# booz_imu.net
KiCad netlist of a schematic drawn in EAGLE
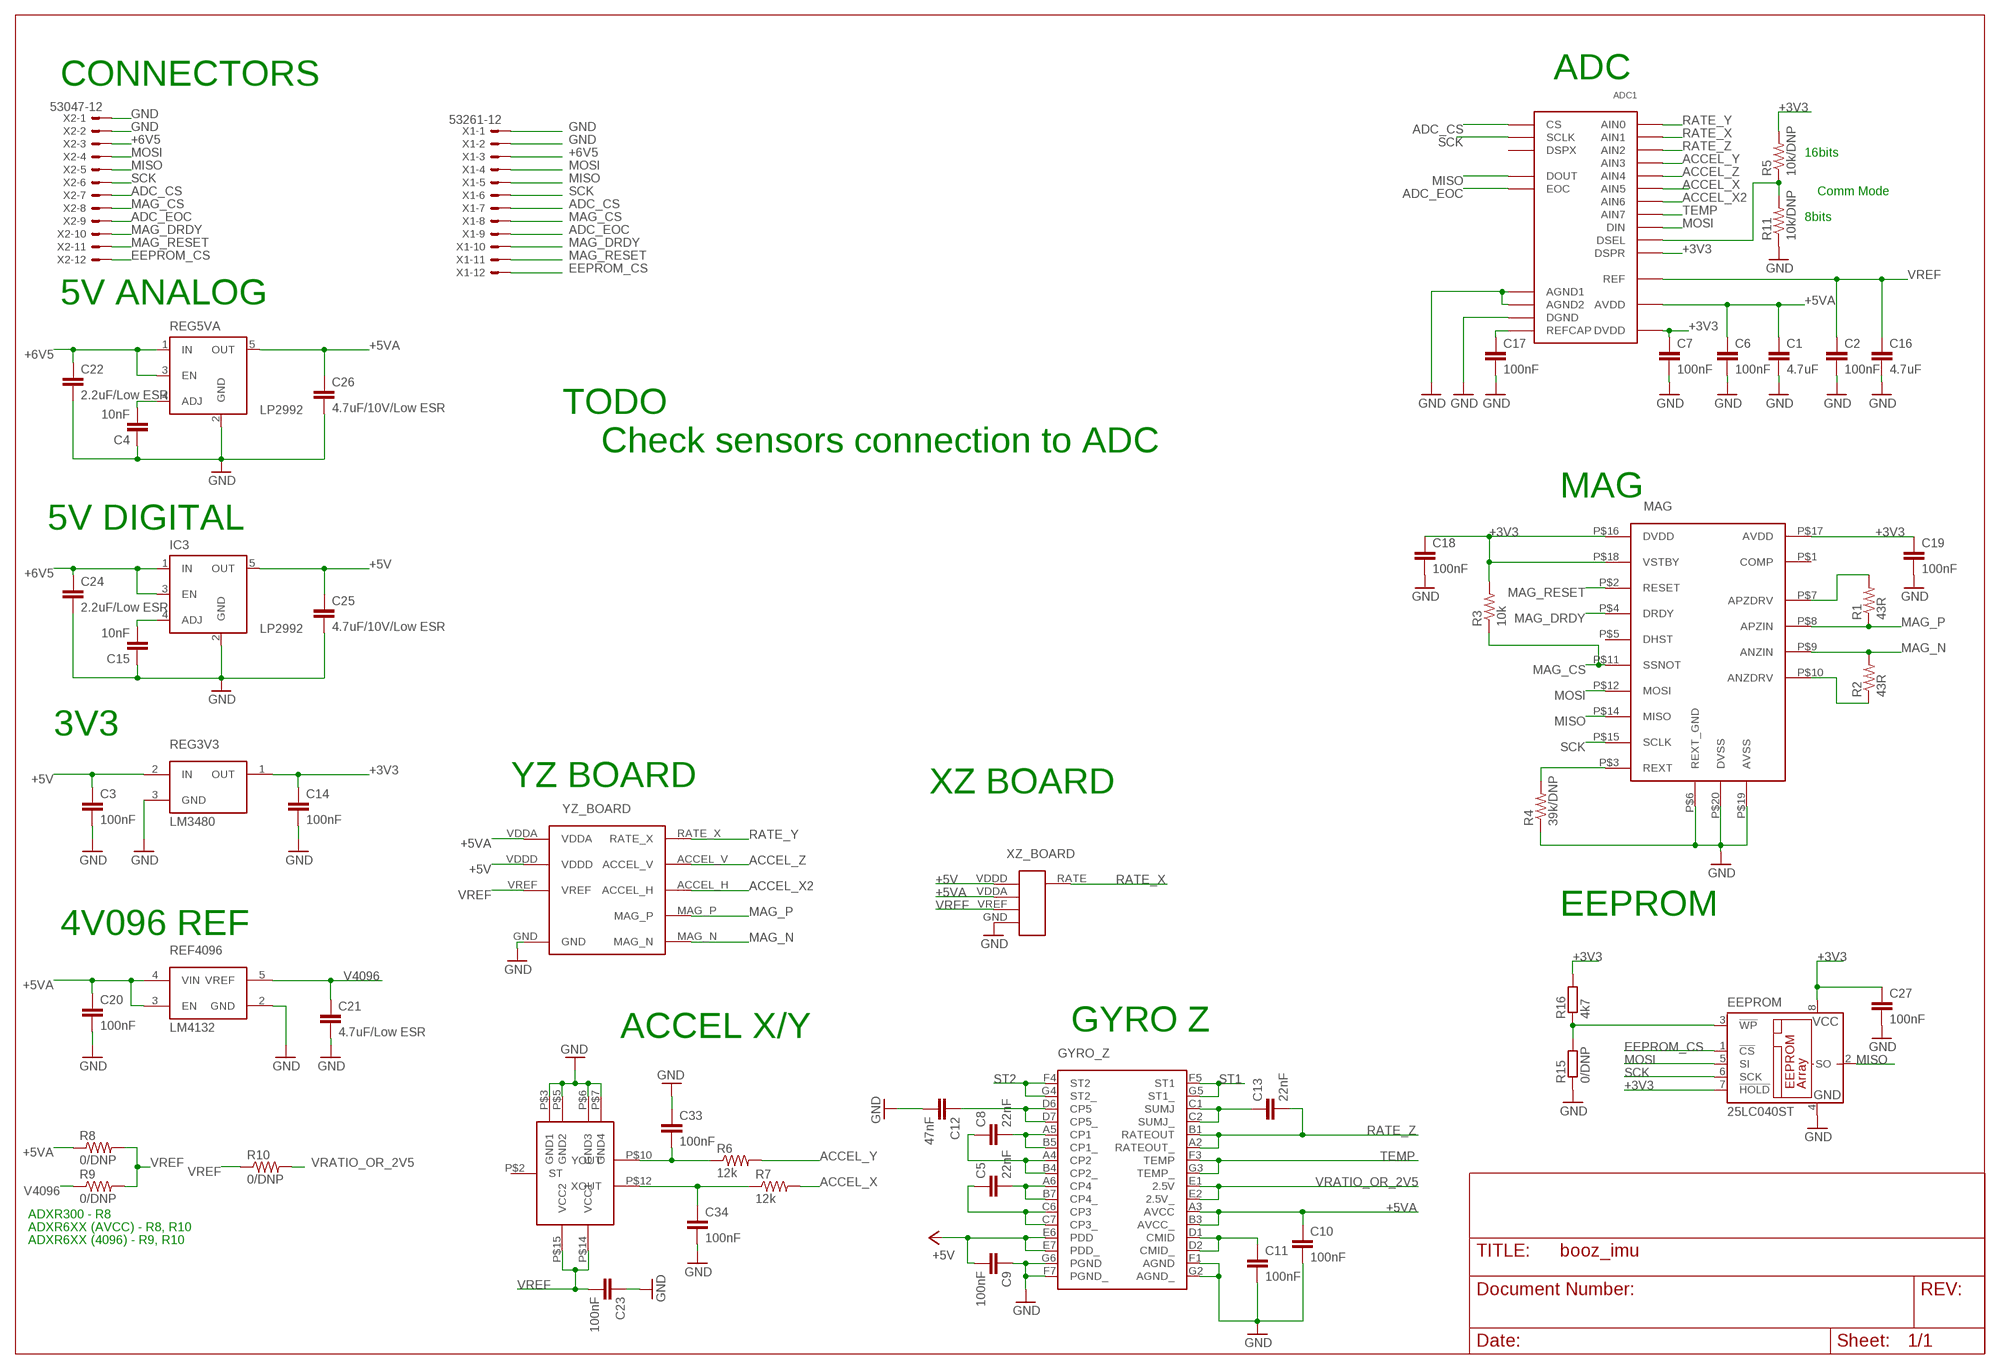
[diagram p0: schematic, sheet 1]

(export (version "E")
  (design (tool "Eeschema 10.0.6"))
  (components
    (comp (ref "ADC1")
      (value "MAX1168")
      (footprint "eagle-import:QSOP24")
      (libsource (lib "eagle-import") (part "MAX1168"))
    )
    (comp (ref "C1")
      (value "4.7uF")
      (footprint "eagle-import:C0805")
      (libsource (lib "eagle-import") (part "C-EUC0805"))
    )
    (comp (ref "C2")
      (value "100nF")
      (footprint "eagle-import:C0603K")
      (libsource (lib "eagle-import") (part "C-EUC0603K"))
    )
    (comp (ref "C3")
      (value "100nF")
      (footprint "eagle-import:C0603K")
      (libsource (lib "eagle-import") (part "C-EUC0603K"))
    )
    (comp (ref "C4")
      (value "10nF")
      (footprint "eagle-import:C0603K")
      (libsource (lib "eagle-import") (part "C-EUC0603K"))
    )
    (comp (ref "C5")
      (value "22nF")
      (footprint "eagle-import:C0603K")
      (libsource (lib "eagle-import") (part "C-EUC0603K"))
    )
    (comp (ref "C6")
      (value "100nF")
      (footprint "eagle-import:C0603K")
      (libsource (lib "eagle-import") (part "C-EUC0603K"))
    )
    (comp (ref "C7")
      (value "100nF")
      (footprint "eagle-import:C0603K")
      (libsource (lib "eagle-import") (part "C-EUC0603K"))
    )
    (comp (ref "C8")
      (value "22nF")
      (footprint "eagle-import:C0603K")
      (libsource (lib "eagle-import") (part "C-EUC0603K"))
    )
    (comp (ref "C9")
      (value "100nF")
      (footprint "eagle-import:C0603K")
      (libsource (lib "eagle-import") (part "C-EUC0603K"))
    )
    (comp (ref "C10")
      (value "100nF")
      (footprint "eagle-import:C0603K")
      (libsource (lib "eagle-import") (part "C-EUC0603K"))
    )
    (comp (ref "C11")
      (value "100nF")
      (footprint "eagle-import:C0603K")
      (libsource (lib "eagle-import") (part "C-EUC0603K"))
    )
    (comp (ref "C12")
      (value "47nF")
      (footprint "eagle-import:C0603K")
      (libsource (lib "eagle-import") (part "C-EUC0603K"))
    )
    (comp (ref "C13")
      (value "22nF")
      (footprint "eagle-import:C0603K")
      (libsource (lib "eagle-import") (part "C-EUC0603K"))
    )
    (comp (ref "C14")
      (value "100nF")
      (footprint "eagle-import:C0603K")
      (libsource (lib "eagle-import") (part "C-EUC0603K"))
    )
    (comp (ref "C15")
      (value "10nF")
      (footprint "eagle-import:C0603K")
      (libsource (lib "eagle-import") (part "C-EUC0603K"))
    )
    (comp (ref "C16")
      (value "4.7uF")
      (footprint "eagle-import:C0805")
      (libsource (lib "eagle-import") (part "C-EUC0805"))
    )
    (comp (ref "C17")
      (value "100nF")
      (footprint "eagle-import:C0603K")
      (libsource (lib "eagle-import") (part "C-EUC0603K"))
    )
    (comp (ref "C18")
      (value "100nF")
      (footprint "eagle-import:C0603K")
      (libsource (lib "eagle-import") (part "C-EUC0603K"))
    )
    (comp (ref "C19")
      (value "100nF")
      (footprint "eagle-import:C0603K")
      (libsource (lib "eagle-import") (part "C-EUC0603K"))
    )
    (comp (ref "C20")
      (value "100nF")
      (footprint "eagle-import:C0603K")
      (libsource (lib "eagle-import") (part "C-EUC0603K"))
    )
    (comp (ref "C21")
      (value "4.7uF/Low ESR")
      (footprint "eagle-import:C0805K")
      (libsource (lib "eagle-import") (part "C-EUC0805K"))
    )
    (comp (ref "C22")
      (value "2.2uF/Low ESR")
      (footprint "eagle-import:C0603K")
      (libsource (lib "eagle-import") (part "C-EUC0603K"))
    )
    (comp (ref "C23")
      (value "100nF")
      (footprint "eagle-import:C0603K")
      (libsource (lib "eagle-import") (part "C-EUC0603K"))
    )
    (comp (ref "C24")
      (value "2.2uF/Low ESR")
      (footprint "eagle-import:C0603K")
      (libsource (lib "eagle-import") (part "C-EUC0603K"))
    )
    (comp (ref "C25")
      (value "4.7uF/10V/Low ESR")
      (footprint "eagle-import:C0805K")
      (libsource (lib "eagle-import") (part "C-EUC0805K"))
    )
    (comp (ref "C26")
      (value "4.7uF/10V/Low ESR")
      (footprint "eagle-import:C0805K")
      (libsource (lib "eagle-import") (part "C-EUC0805K"))
    )
    (comp (ref "C27")
      (value "100nF")
      (footprint "eagle-import:C0603")
      (libsource (lib "eagle-import") (part "C-EUC0603"))
    )
    (comp (ref "C33")
      (value "100nF")
      (footprint "eagle-import:C0603K")
      (libsource (lib "eagle-import") (part "C-EUC0603K"))
    )
    (comp (ref "C34")
      (value "100nF")
      (footprint "eagle-import:C0603K")
      (libsource (lib "eagle-import") (part "C-EUC0603K"))
    )
    (comp (ref "EEPROM")
      (value "25LC040ST")
      (footprint "eagle-import:TSSOP8")
      (libsource (lib "eagle-import") (part "25STLC040"))
    )
    (comp (ref "GYRO_Z")
      (value "ADXR")
      (footprint "eagle-import:BC-32")
      (libsource (lib "eagle-import") (part "ADXR"))
    )
    (comp (ref "IC3")
      (value "LP2992")
      (footprint "eagle-import:SOT23-5")
      (libsource (lib "eagle-import") (part "MIC5219BM5"))
    )
    (comp (ref "MAG")
      (value "MS2100")
      (footprint "eagle-import:QFN20")
      (libsource (lib "eagle-import") (part "MS2100"))
    )
    (comp (ref "R1")
      (value "43R")
      (footprint "eagle-import:R0603")
      (libsource (lib "eagle-import") (part "R-US_R0603"))
    )
    (comp (ref "R2")
      (value "43R")
      (footprint "eagle-import:R0603")
      (libsource (lib "eagle-import") (part "R-US_R0603"))
    )
    (comp (ref "R3")
      (value "10k")
      (footprint "eagle-import:R0603")
      (libsource (lib "eagle-import") (part "R-US_R0603"))
    )
    (comp (ref "R4")
      (value "39k/DNP")
      (footprint "eagle-import:R0603")
      (libsource (lib "eagle-import") (part "R-US_R0603"))
    )
    (comp (ref "R5")
      (value "10k/DNP")
      (footprint "eagle-import:R0603")
      (libsource (lib "eagle-import") (part "R-US_R0603"))
    )
    (comp (ref "R6")
      (value "12k")
      (footprint "eagle-import:R0603")
      (libsource (lib "eagle-import") (part "R-US_R0603"))
    )
    (comp (ref "R7")
      (value "12k")
      (footprint "eagle-import:R0603")
      (libsource (lib "eagle-import") (part "R-US_R0603"))
    )
    (comp (ref "R8")
      (value "0/DNP")
      (footprint "eagle-import:R0603")
      (libsource (lib "eagle-import") (part "R-US_R0603"))
    )
    (comp (ref "R9")
      (value "0/DNP")
      (footprint "eagle-import:R0603")
      (libsource (lib "eagle-import") (part "R-US_R0603"))
    )
    (comp (ref "R10")
      (value "0/DNP")
      (footprint "eagle-import:R0603")
      (libsource (lib "eagle-import") (part "R-US_R0603"))
    )
    (comp (ref "R11")
      (value "10k/DNP")
      (footprint "eagle-import:R0603")
      (libsource (lib "eagle-import") (part "R-US_R0603"))
    )
    (comp (ref "R15")
      (value "0/DNP")
      (footprint "eagle-import:R0603")
      (libsource (lib "eagle-import") (part "R-EU_R0603"))
    )
    (comp (ref "R16")
      (value "4k7")
      (footprint "eagle-import:R0603")
      (libsource (lib "eagle-import") (part "R-EU_R0603"))
    )
    (comp (ref "REF4096")
      (value "LM4132")
      (footprint "eagle-import:SOT23-5L")
      (libsource (lib "eagle-import") (part "LM4132"))
    )
    (comp (ref "REG3V3")
      (value "LM3480")
      (footprint "eagle-import:SOT23")
      (libsource (lib "eagle-import") (part "LM3480"))
    )
    (comp (ref "REG5VA")
      (value "LP2992")
      (footprint "eagle-import:SOT23-5")
      (libsource (lib "eagle-import") (part "MIC5219BM5"))
    )
    (comp (ref "U$2")
      (value "ADXL320")
      (footprint "eagle-import:LSCFP")
      (libsource (lib "eagle-import") (part "ADXL320"))
    )
    (comp (ref "X1")
      (value "53261-12")
      (footprint "eagle-import:53261-12")
      (libsource (lib "eagle-import") (part "53?-12261"))
    )
    (comp (ref "X2")
      (value "53047-12")
      (footprint "eagle-import:53047-12")
      (libsource (lib "eagle-import") (part "53?-12047"))
    )
    (comp (ref "XZ_BOARD")
      (value "IMU_XZ_2")
      (footprint "eagle-import:IMU_XZ")
      (libsource (lib "eagle-import") (part "IMU_XZ_2"))
    )
    (comp (ref "YZ_BOARD")
      (value "IMU_YZ_MAG_2")
      (footprint "eagle-import:IMU_YZ_MAG")
      (libsource (lib "eagle-import") (part "IMU_YZ_MAG_2"))
    )
  )
  (nets
    (net (code "1") (name "+5V") (class "Default")
      (node (ref "C25") (pin "1") (pinfunction "1_1") (pintype "passive"))
      (node (ref "C3") (pin "1") (pinfunction "1_1") (pintype "passive"))
      (node (ref "C9") (pin "2") (pinfunction "2_2") (pintype "passive"))
      (node (ref "GYRO_Z") (pin "E6") (pinfunction "PDD_E6") (pintype "bidirectional"))
      (node (ref "GYRO_Z") (pin "E7") (pinfunction "PDD__E7") (pintype "bidirectional"))
      (node (ref "IC3") (pin "5") (pinfunction "OUT_5") (pintype "output"))
      (node (ref "REG3V3") (pin "2") (pinfunction "IN_2") (pintype "power_in"))
      (node (ref "XZ_BOARD") (pin "VDDD") (pinfunction "VDDD_VDDD") (pintype "bidirectional"))
      (node (ref "YZ_BOARD") (pin "VDDD") (pinfunction "VDDD_VDDD") (pintype "bidirectional"))
    )
    (net (code "2") (name "/+3V3") (class "Default")
      (node (ref "ADC1") (pin "P$1") (pinfunction "DSPR_P$1") (pintype "bidirectional"))
      (node (ref "ADC1") (pin "P$22") (pinfunction "DVDD_P$22") (pintype "bidirectional"))
      (node (ref "C14") (pin "1") (pinfunction "1_1") (pintype "passive"))
      (node (ref "C18") (pin "1") (pinfunction "1_1") (pintype "passive"))
      (node (ref "C19") (pin "1") (pinfunction "1_1") (pintype "passive"))
      (node (ref "C27") (pin "1") (pinfunction "1_1") (pintype "passive"))
      (node (ref "C7") (pin "1") (pinfunction "1_1") (pintype "passive"))
      (node (ref "EEPROM") (pin "7") (pinfunction "~{HOLD}_7") (pintype "input"))
      (node (ref "EEPROM") (pin "8") (pinfunction "VCC_8") (pintype "power_in"))
      (node (ref "MAG") (pin "P$16") (pinfunction "DVDD_P$16") (pintype "bidirectional"))
      (node (ref "MAG") (pin "P$17") (pinfunction "AVDD_P$17") (pintype "bidirectional"))
      (node (ref "MAG") (pin "P$18") (pinfunction "VSTBY_P$18") (pintype "bidirectional"))
      (node (ref "R16") (pin "2") (pinfunction "2_2") (pintype "passive"))
      (node (ref "R3") (pin "2") (pinfunction "2_2") (pintype "passive"))
      (node (ref "R5") (pin "2") (pinfunction "2_2") (pintype "passive"))
      (node (ref "REG3V3") (pin "1") (pinfunction "OUT_1") (pintype "power_in"))
    )
    (net (code "3") (name "/+5VA") (class "Default")
      (node (ref "ADC1") (pin "P$19") (pinfunction "AVDD_P$19") (pintype "bidirectional"))
      (node (ref "C1") (pin "1") (pinfunction "1_1") (pintype "passive"))
      (node (ref "C10") (pin "1") (pinfunction "1_1") (pintype "passive"))
      (node (ref "C20") (pin "1") (pinfunction "1_1") (pintype "passive"))
      (node (ref "C26") (pin "1") (pinfunction "1_1") (pintype "passive"))
      (node (ref "C6") (pin "1") (pinfunction "1_1") (pintype "passive"))
      (node (ref "GYRO_Z") (pin "A3") (pinfunction "AVCC_A3") (pintype "bidirectional"))
      (node (ref "GYRO_Z") (pin "B3") (pinfunction "AVCC__B3") (pintype "bidirectional"))
      (node (ref "R8") (pin "1") (pinfunction "1_1") (pintype "passive"))
      (node (ref "REF4096") (pin "3") (pinfunction "EN_3") (pintype "bidirectional"))
      (node (ref "REF4096") (pin "4") (pinfunction "VIN_4") (pintype "power_in"))
      (node (ref "REG5VA") (pin "5") (pinfunction "OUT_5") (pintype "output"))
      (node (ref "XZ_BOARD") (pin "VDDA") (pinfunction "VDDA_VDDA") (pintype "bidirectional"))
      (node (ref "YZ_BOARD") (pin "VDDA") (pinfunction "VDDA_VDDA") (pintype "bidirectional"))
    )
    (net (code "4") (name "/+6V5") (class "Default")
      (node (ref "C22") (pin "1") (pinfunction "1_1") (pintype "passive"))
      (node (ref "C24") (pin "1") (pinfunction "1_1") (pintype "passive"))
      (node (ref "IC3") (pin "1") (pinfunction "IN_1") (pintype "input"))
      (node (ref "IC3") (pin "3") (pinfunction "EN_3") (pintype "input"))
      (node (ref "REG5VA") (pin "1") (pinfunction "IN_1") (pintype "input"))
      (node (ref "REG5VA") (pin "3") (pinfunction "EN_3") (pintype "input"))
      (node (ref "X1") (pin "3") (pinfunction "S_3") (pintype "passive"))
      (node (ref "X2") (pin "3") (pinfunction "S_3") (pintype "passive"))
    )
    (net (code "5") (name "/ACCEL_X") (class "Default")
      (node (ref "ADC1") (pin "P$12") (pinfunction "AIN5_P$12") (pintype "bidirectional"))
      (node (ref "R7") (pin "2") (pinfunction "2_2") (pintype "passive"))
    )
    (net (code "6") (name "/ACCEL_X2") (class "Default")
      (node (ref "ADC1") (pin "P$13") (pinfunction "AIN6_P$13") (pintype "bidirectional"))
      (node (ref "YZ_BOARD") (pin "ACCEL_H") (pinfunction "ACCEL_H_ACCEL_H") (pintype "bidirectional"))
    )
    (net (code "7") (name "/ACCEL_Y") (class "Default")
      (node (ref "ADC1") (pin "P$10") (pinfunction "AIN3_P$10") (pintype "bidirectional"))
      (node (ref "R6") (pin "2") (pinfunction "2_2") (pintype "passive"))
    )
    (net (code "8") (name "/ACCEL_Z") (class "Default")
      (node (ref "ADC1") (pin "P$11") (pinfunction "AIN4_P$11") (pintype "bidirectional"))
      (node (ref "YZ_BOARD") (pin "ACCEL_V") (pinfunction "ACCEL_V_ACCEL_V") (pintype "bidirectional"))
    )
    (net (code "9") (name "/ADC_CS") (class "Default")
      (node (ref "ADC1") (pin "P$20") (pinfunction "CS_P$20") (pintype "bidirectional"))
      (node (ref "X1") (pin "7") (pinfunction "S_7") (pintype "passive"))
      (node (ref "X2") (pin "7") (pinfunction "S_7") (pintype "passive"))
    )
    (net (code "10") (name "/ADC_EOC") (class "Default")
      (node (ref "ADC1") (pin "P$6") (pinfunction "EOC_P$6") (pintype "bidirectional"))
      (node (ref "X1") (pin "9") (pinfunction "S_9") (pintype "passive"))
      (node (ref "X2") (pin "9") (pinfunction "S_9") (pintype "passive"))
    )
    (net (code "11") (name "/EEPROM_CS") (class "Default")
      (node (ref "EEPROM") (pin "1") (pinfunction "~{CS}_1") (pintype "input"))
      (node (ref "X1") (pin "12") (pinfunction "S_12") (pintype "passive"))
      (node (ref "X2") (pin "12") (pinfunction "S_12") (pintype "passive"))
    )
    (net (code "12") (name "/MAG_CS") (class "Default")
      (node (ref "MAG") (pin "P$11") (pinfunction "SSNOT_P$11") (pintype "bidirectional"))
      (node (ref "R3") (pin "1") (pinfunction "1_1") (pintype "passive"))
      (node (ref "X1") (pin "8") (pinfunction "S_8") (pintype "passive"))
      (node (ref "X2") (pin "8") (pinfunction "S_8") (pintype "passive"))
    )
    (net (code "13") (name "/MAG_DRDY") (class "Default")
      (node (ref "MAG") (pin "P$4") (pinfunction "DRDY_P$4") (pintype "bidirectional"))
      (node (ref "X1") (pin "10") (pinfunction "S_10") (pintype "passive"))
      (node (ref "X2") (pin "10") (pinfunction "S_10") (pintype "passive"))
    )
    (net (code "14") (name "/MAG_N") (class "Default")
      (node (ref "MAG") (pin "P$9") (pinfunction "ANZIN_P$9") (pintype "bidirectional"))
      (node (ref "R2") (pin "2") (pinfunction "2_2") (pintype "passive"))
      (node (ref "YZ_BOARD") (pin "MAG_N") (pinfunction "MAG_N_MAG_N") (pintype "bidirectional"))
    )
    (net (code "15") (name "/MAG_P") (class "Default")
      (node (ref "MAG") (pin "P$8") (pinfunction "APZIN_P$8") (pintype "bidirectional"))
      (node (ref "R1") (pin "1") (pinfunction "1_1") (pintype "passive"))
      (node (ref "YZ_BOARD") (pin "MAG_P") (pinfunction "MAG_P_MAG_P") (pintype "bidirectional"))
    )
    (net (code "16") (name "/MAG_RESET") (class "Default")
      (node (ref "MAG") (pin "P$2") (pinfunction "RESET_P$2") (pintype "bidirectional"))
      (node (ref "X1") (pin "11") (pinfunction "S_11") (pintype "passive"))
      (node (ref "X2") (pin "11") (pinfunction "S_11") (pintype "passive"))
    )
    (net (code "17") (name "/MISO") (class "Default")
      (node (ref "ADC1") (pin "P$3") (pinfunction "DOUT_P$3") (pintype "bidirectional"))
      (node (ref "EEPROM") (pin "2") (pinfunction "SO_2") (pintype "bidirectional"))
      (node (ref "MAG") (pin "P$14") (pinfunction "MISO_P$14") (pintype "bidirectional"))
      (node (ref "X1") (pin "5") (pinfunction "S_5") (pintype "passive"))
      (node (ref "X2") (pin "5") (pinfunction "S_5") (pintype "passive"))
    )
    (net (code "18") (name "/MOSI") (class "Default")
      (node (ref "ADC1") (pin "P$5") (pinfunction "DIN_P$5") (pintype "bidirectional"))
      (node (ref "EEPROM") (pin "5") (pinfunction "SI_5") (pintype "input"))
      (node (ref "MAG") (pin "P$12") (pinfunction "MOSI_P$12") (pintype "bidirectional"))
      (node (ref "X1") (pin "4") (pinfunction "S_4") (pintype "passive"))
      (node (ref "X2") (pin "4") (pinfunction "S_4") (pintype "passive"))
    )
    (net (code "19") (name "/RATE_X") (class "Default")
      (node (ref "ADC1") (pin "P$8") (pinfunction "AIN1_P$8") (pintype "bidirectional"))
      (node (ref "XZ_BOARD") (pin "RATE") (pinfunction "RATE_RATE") (pintype "bidirectional"))
    )
    (net (code "20") (name "/RATE_Y") (class "Default")
      (node (ref "ADC1") (pin "P$7") (pinfunction "AIN0_P$7") (pintype "bidirectional"))
      (node (ref "YZ_BOARD") (pin "RATE_X") (pinfunction "RATE_X_RATE_X") (pintype "bidirectional"))
    )
    (net (code "21") (name "/RATE_Z") (class "Default")
      (node (ref "ADC1") (pin "P$9") (pinfunction "AIN2_P$9") (pintype "bidirectional"))
      (node (ref "C13") (pin "2") (pinfunction "2_2") (pintype "passive"))
      (node (ref "GYRO_Z") (pin "A2") (pinfunction "RATEOUT__A2") (pintype "bidirectional"))
      (node (ref "GYRO_Z") (pin "B1") (pinfunction "RATEOUT_B1") (pintype "bidirectional"))
    )
    (net (code "22") (name "/SCK") (class "Default")
      (node (ref "ADC1") (pin "P$4") (pinfunction "SCLK_P$4") (pintype "bidirectional"))
      (node (ref "EEPROM") (pin "6") (pinfunction "SCK_6") (pintype "input"))
      (node (ref "MAG") (pin "P$15") (pinfunction "SCLK_P$15") (pintype "bidirectional"))
      (node (ref "X1") (pin "6") (pinfunction "S_6") (pintype "passive"))
      (node (ref "X2") (pin "6") (pinfunction "S_6") (pintype "passive"))
    )
    (net (code "23") (name "/ST1") (class "Default")
      (node (ref "GYRO_Z") (pin "F5") (pinfunction "ST1_F5") (pintype "bidirectional"))
      (node (ref "GYRO_Z") (pin "G5") (pinfunction "ST1__G5") (pintype "bidirectional"))
    )
    (net (code "24") (name "/ST2") (class "Default")
      (node (ref "GYRO_Z") (pin "F4") (pinfunction "ST2_F4") (pintype "bidirectional"))
      (node (ref "GYRO_Z") (pin "G4") (pinfunction "ST2__G4") (pintype "bidirectional"))
    )
    (net (code "25") (name "/TEMP") (class "Default")
      (node (ref "ADC1") (pin "P$14") (pinfunction "AIN7_P$14") (pintype "bidirectional"))
      (node (ref "GYRO_Z") (pin "F3") (pinfunction "TEMP_F3") (pintype "bidirectional"))
      (node (ref "GYRO_Z") (pin "G3") (pinfunction "TEMP__G3") (pintype "bidirectional"))
    )
    (net (code "26") (name "/V4096") (class "Default")
      (node (ref "C21") (pin "1") (pinfunction "1_1") (pintype "passive"))
      (node (ref "R9") (pin "1") (pinfunction "1_1") (pintype "passive"))
      (node (ref "REF4096") (pin "5") (pinfunction "VREF_5") (pintype "power_in"))
    )
    (net (code "27") (name "/VRATIO_OR_2V5") (class "Default")
      (node (ref "GYRO_Z") (pin "E1") (pinfunction "2.5V_E1") (pintype "bidirectional"))
      (node (ref "GYRO_Z") (pin "E2") (pinfunction "2.5V__E2") (pintype "bidirectional"))
      (node (ref "R10") (pin "2") (pinfunction "2_2") (pintype "passive"))
    )
    (net (code "28") (name "/VREF") (class "Default")
      (node (ref "ADC1") (pin "P$15") (pinfunction "REF_P$15") (pintype "bidirectional"))
      (node (ref "C16") (pin "1") (pinfunction "1_1") (pintype "passive"))
      (node (ref "C2") (pin "1") (pinfunction "1_1") (pintype "passive"))
      (node (ref "C23") (pin "2") (pinfunction "2_2") (pintype "passive"))
      (node (ref "R10") (pin "1") (pinfunction "1_1") (pintype "passive"))
      (node (ref "R8") (pin "2") (pinfunction "2_2") (pintype "passive"))
      (node (ref "R9") (pin "2") (pinfunction "2_2") (pintype "passive"))
      (node (ref "U$2") (pin "P$14") (pinfunction "VCC1_P$14") (pintype "bidirectional"))
      (node (ref "U$2") (pin "P$15") (pinfunction "VCC2_P$15") (pintype "bidirectional"))
      (node (ref "XZ_BOARD") (pin "VREF") (pinfunction "VREF_VREF") (pintype "bidirectional"))
      (node (ref "YZ_BOARD") (pin "VREF") (pinfunction "VREF_VREF") (pintype "bidirectional"))
    )
    (net (code "29") (name "GND") (class "Default")
      (node (ref "ADC1") (pin "P$17") (pinfunction "AGND1_P$17") (pintype "bidirectional"))
      (node (ref "ADC1") (pin "P$18") (pinfunction "AGND2_P$18") (pintype "bidirectional"))
      (node (ref "ADC1") (pin "P$21") (pinfunction "DGND_P$21") (pintype "bidirectional"))
      (node (ref "C1") (pin "2") (pinfunction "2_2") (pintype "passive"))
      (node (ref "C10") (pin "2") (pinfunction "2_2") (pintype "passive"))
      (node (ref "C11") (pin "2") (pinfunction "2_2") (pintype "passive"))
      (node (ref "C12") (pin "2") (pinfunction "2_2") (pintype "passive"))
      (node (ref "C14") (pin "2") (pinfunction "2_2") (pintype "passive"))
      (node (ref "C15") (pin "1") (pinfunction "1_1") (pintype "passive"))
      (node (ref "C16") (pin "2") (pinfunction "2_2") (pintype "passive"))
      (node (ref "C17") (pin "2") (pinfunction "2_2") (pintype "passive"))
      (node (ref "C18") (pin "2") (pinfunction "2_2") (pintype "passive"))
      (node (ref "C19") (pin "2") (pinfunction "2_2") (pintype "passive"))
      (node (ref "C2") (pin "2") (pinfunction "2_2") (pintype "passive"))
      (node (ref "C20") (pin "2") (pinfunction "2_2") (pintype "passive"))
      (node (ref "C21") (pin "2") (pinfunction "2_2") (pintype "passive"))
      (node (ref "C22") (pin "2") (pinfunction "2_2") (pintype "passive"))
      (node (ref "C23") (pin "1") (pinfunction "1_1") (pintype "passive"))
      (node (ref "C24") (pin "2") (pinfunction "2_2") (pintype "passive"))
      (node (ref "C25") (pin "2") (pinfunction "2_2") (pintype "passive"))
      (node (ref "C26") (pin "2") (pinfunction "2_2") (pintype "passive"))
      (node (ref "C27") (pin "2") (pinfunction "2_2") (pintype "passive"))
      (node (ref "C3") (pin "2") (pinfunction "2_2") (pintype "passive"))
      (node (ref "C33") (pin "1") (pinfunction "1_1") (pintype "passive"))
      (node (ref "C34") (pin "2") (pinfunction "2_2") (pintype "passive"))
      (node (ref "C4") (pin "1") (pinfunction "1_1") (pintype "passive"))
      (node (ref "C6") (pin "2") (pinfunction "2_2") (pintype "passive"))
      (node (ref "C7") (pin "2") (pinfunction "2_2") (pintype "passive"))
      (node (ref "C9") (pin "1") (pinfunction "1_1") (pintype "passive"))
      (node (ref "EEPROM") (pin "4") (pinfunction "GND_4") (pintype "power_in"))
      (node (ref "GYRO_Z") (pin "F1") (pinfunction "AGND_F1") (pintype "bidirectional"))
      (node (ref "GYRO_Z") (pin "F7") (pinfunction "PGND__F7") (pintype "bidirectional"))
      (node (ref "GYRO_Z") (pin "G2") (pinfunction "AGND__G2") (pintype "bidirectional"))
      (node (ref "GYRO_Z") (pin "G6") (pinfunction "PGND_G6") (pintype "bidirectional"))
      (node (ref "IC3") (pin "2") (pinfunction "GND_2") (pintype "power_in"))
      (node (ref "MAG") (pin "P$19") (pinfunction "AVSS_P$19") (pintype "bidirectional"))
      (node (ref "MAG") (pin "P$20") (pinfunction "DVSS_P$20") (pintype "bidirectional"))
      (node (ref "MAG") (pin "P$6") (pinfunction "REXT_GND_P$6") (pintype "bidirectional"))
      (node (ref "R11") (pin "1") (pinfunction "1_1") (pintype "passive"))
      (node (ref "R15") (pin "1") (pinfunction "1_1") (pintype "passive"))
      (node (ref "R4") (pin "1") (pinfunction "1_1") (pintype "passive"))
      (node (ref "REF4096") (pin "2") (pinfunction "GND_2") (pintype "power_in"))
      (node (ref "REG3V3") (pin "3") (pinfunction "GND_3") (pintype "power_in"))
      (node (ref "REG5VA") (pin "2") (pinfunction "GND_2") (pintype "power_in"))
      (node (ref "U$2") (pin "P$3") (pinfunction "GND1_P$3") (pintype "bidirectional"))
      (node (ref "U$2") (pin "P$5") (pinfunction "GND2_P$5") (pintype "bidirectional"))
      (node (ref "U$2") (pin "P$6") (pinfunction "GND3_P$6") (pintype "bidirectional"))
      (node (ref "U$2") (pin "P$7") (pinfunction "GND4_P$7") (pintype "bidirectional"))
      (node (ref "X1") (pin "1") (pinfunction "S_1") (pintype "passive"))
      (node (ref "X1") (pin "2") (pinfunction "S_2") (pintype "passive"))
      (node (ref "X2") (pin "1") (pinfunction "S_1") (pintype "passive"))
      (node (ref "X2") (pin "2") (pinfunction "S_2") (pintype "passive"))
      (node (ref "XZ_BOARD") (pin "GND") (pinfunction "GND_GND") (pintype "bidirectional"))
      (node (ref "YZ_BOARD") (pin "GND") (pinfunction "GND_GND") (pintype "bidirectional"))
    )
    (net (code "30") (name "Net-(ADC1-DSEL)") (class "Default")
      (node (ref "ADC1") (pin "P$2") (pinfunction "DSEL_P$2") (pintype "bidirectional"))
      (node (ref "R11") (pin "2") (pinfunction "2_2") (pintype "passive"))
      (node (ref "R5") (pin "1") (pinfunction "1_1") (pintype "passive"))
    )
    (net (code "31") (name "Net-(ADC1-REFCAP)") (class "Default")
      (node (ref "ADC1") (pin "P$16") (pinfunction "REFCAP_P$16") (pintype "bidirectional"))
      (node (ref "C17") (pin "1") (pinfunction "1_1") (pintype "passive"))
    )
    (net (code "32") (name "Net-(EEPROM-~{WP})") (class "Default")
      (node (ref "EEPROM") (pin "3") (pinfunction "~{WP}_3") (pintype "input"))
      (node (ref "R15") (pin "2") (pinfunction "2_2") (pintype "passive"))
      (node (ref "R16") (pin "1") (pinfunction "1_1") (pintype "passive"))
    )
    (net (code "33") (name "Net-(GYRO_Z-CMID)") (class "Default")
      (node (ref "C11") (pin "1") (pinfunction "1_1") (pintype "passive"))
      (node (ref "GYRO_Z") (pin "D1") (pinfunction "CMID_D1") (pintype "bidirectional"))
      (node (ref "GYRO_Z") (pin "D2") (pinfunction "CMID__D2") (pintype "bidirectional"))
    )
    (net (code "34") (name "Net-(GYRO_Z-CP1)") (class "Default")
      (node (ref "C8") (pin "2") (pinfunction "2_2") (pintype "passive"))
      (node (ref "GYRO_Z") (pin "A5") (pinfunction "CP1_A5") (pintype "bidirectional"))
      (node (ref "GYRO_Z") (pin "B5") (pinfunction "CP1__B5") (pintype "bidirectional"))
    )
    (net (code "35") (name "Net-(GYRO_Z-CP2)") (class "Default")
      (node (ref "C8") (pin "1") (pinfunction "1_1") (pintype "passive"))
      (node (ref "GYRO_Z") (pin "A4") (pinfunction "CP2_A4") (pintype "bidirectional"))
      (node (ref "GYRO_Z") (pin "B4") (pinfunction "CP2__B4") (pintype "bidirectional"))
    )
    (net (code "36") (name "Net-(GYRO_Z-CP3)") (class "Default")
      (node (ref "C5") (pin "1") (pinfunction "1_1") (pintype "passive"))
      (node (ref "GYRO_Z") (pin "C6") (pinfunction "CP3_C6") (pintype "bidirectional"))
      (node (ref "GYRO_Z") (pin "C7") (pinfunction "CP3__C7") (pintype "bidirectional"))
    )
    (net (code "37") (name "Net-(GYRO_Z-CP4)") (class "Default")
      (node (ref "C5") (pin "2") (pinfunction "2_2") (pintype "passive"))
      (node (ref "GYRO_Z") (pin "A6") (pinfunction "CP4_A6") (pintype "bidirectional"))
      (node (ref "GYRO_Z") (pin "B7") (pinfunction "CP4__B7") (pintype "bidirectional"))
    )
    (net (code "38") (name "Net-(GYRO_Z-CP5)") (class "Default")
      (node (ref "C12") (pin "1") (pinfunction "1_1") (pintype "passive"))
      (node (ref "GYRO_Z") (pin "D6") (pinfunction "CP5_D6") (pintype "bidirectional"))
      (node (ref "GYRO_Z") (pin "D7") (pinfunction "CP5__D7") (pintype "bidirectional"))
    )
    (net (code "39") (name "Net-(GYRO_Z-SUMJ)") (class "Default")
      (node (ref "C13") (pin "1") (pinfunction "1_1") (pintype "passive"))
      (node (ref "GYRO_Z") (pin "C1") (pinfunction "SUMJ_C1") (pintype "bidirectional"))
      (node (ref "GYRO_Z") (pin "C2") (pinfunction "SUMJ__C2") (pintype "bidirectional"))
    )
    (net (code "40") (name "Net-(IC3-ADJ)") (class "Default")
      (node (ref "C15") (pin "2") (pinfunction "2_2") (pintype "passive"))
      (node (ref "IC3") (pin "4") (pinfunction "ADJ_4") (pintype "passive"))
    )
    (net (code "41") (name "Net-(MAG-ANZDRV)") (class "Default")
      (node (ref "MAG") (pin "P$10") (pinfunction "ANZDRV_P$10") (pintype "bidirectional"))
      (node (ref "R2") (pin "1") (pinfunction "1_1") (pintype "passive"))
    )
    (net (code "42") (name "Net-(MAG-APZDRV)") (class "Default")
      (node (ref "MAG") (pin "P$7") (pinfunction "APZDRV_P$7") (pintype "bidirectional"))
      (node (ref "R1") (pin "2") (pinfunction "2_2") (pintype "passive"))
    )
    (net (code "43") (name "Net-(MAG-REXT)") (class "Default")
      (node (ref "MAG") (pin "P$3") (pinfunction "REXT_P$3") (pintype "bidirectional"))
      (node (ref "R4") (pin "2") (pinfunction "2_2") (pintype "passive"))
    )
    (net (code "44") (name "Net-(REG5VA-ADJ)") (class "Default")
      (node (ref "C4") (pin "2") (pinfunction "2_2") (pintype "passive"))
      (node (ref "REG5VA") (pin "4") (pinfunction "ADJ_4") (pintype "passive"))
    )
    (net (code "45") (name "Net-(U$2-XOUT)") (class "Default")
      (node (ref "C34") (pin "1") (pinfunction "1_1") (pintype "passive"))
      (node (ref "R7") (pin "1") (pinfunction "1_1") (pintype "passive"))
      (node (ref "U$2") (pin "P$12") (pinfunction "XOUT_P$12") (pintype "bidirectional"))
    )
    (net (code "46") (name "Net-(U$2-YOUT)") (class "Default")
      (node (ref "C33") (pin "2") (pinfunction "2_2") (pintype "passive"))
      (node (ref "R6") (pin "1") (pinfunction "1_1") (pintype "passive"))
      (node (ref "U$2") (pin "P$10") (pinfunction "YOUT_P$10") (pintype "bidirectional"))
    )
    (net (code "47") (name "unconnected-(ADC1-DSPX-PadP$23)") (class "Default")
      (node (ref "ADC1") (pin "P$23") (pinfunction "DSPX_P$23") (pintype "bidirectional"))
    )
    (net (code "48") (name "unconnected-(MAG-COMP-PadP$1)") (class "Default")
      (node (ref "MAG") (pin "P$1") (pinfunction "COMP_P$1") (pintype "bidirectional"))
    )
    (net (code "49") (name "unconnected-(MAG-DHST-PadP$5)") (class "Default")
      (node (ref "MAG") (pin "P$5") (pinfunction "DHST_P$5") (pintype "bidirectional"))
    )
    (net (code "50") (name "unconnected-(U$2-ST-PadP$2)") (class "Default")
      (node (ref "U$2") (pin "P$2") (pinfunction "ST_P$2") (pintype "bidirectional"))
    )
  )
)
